# Leaf.net
KiCad netlist of a schematic drawn in Altium Designer
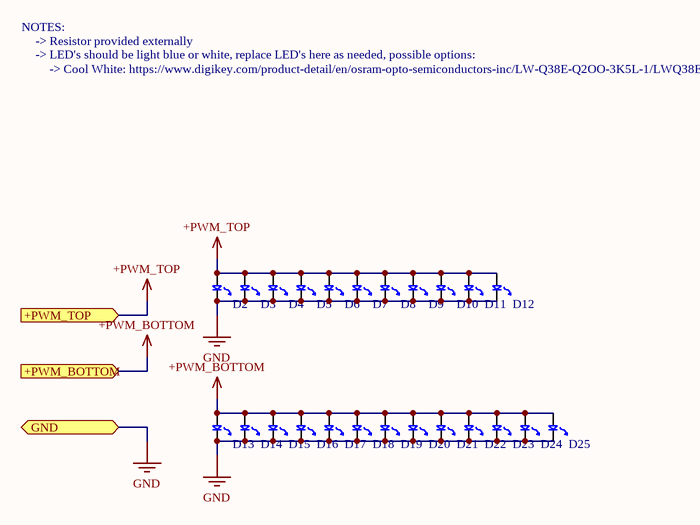
[diagram p0: Leaf.SchDoc]

(export (version "E")
  (design (tool "Eeschema 10.0.6"))
  (components
    (comp (ref "D2")
      (value "LED_LBQ39G_BLUE")
      (footprint "LED_0603P_BLUE")
      (description "Blue 470nm LED Indication - Discrete 2.85V 0603 (1608 Metric)")
      (fields
        (field (name "MANUFACTURER") "OSRAM Opto Semiconductors Inc.")
        (field (name "MANUFACTURER PART NUMBER") "LB Q39G-L2OO-35-1")
      )
      (libsource (lib "SSI") (part "LED_LBQ39G_BLUE"))
    )
    (comp (ref "D3")
      (value "LED_LBQ39G_BLUE")
      (footprint "LED_0603P_BLUE")
      (description "Blue 470nm LED Indication - Discrete 2.85V 0603 (1608 Metric)")
      (fields
        (field (name "MANUFACTURER") "OSRAM Opto Semiconductors Inc.")
        (field (name "MANUFACTURER PART NUMBER") "LB Q39G-L2OO-35-1")
      )
      (libsource (lib "SSI") (part "LED_LBQ39G_BLUE"))
    )
    (comp (ref "D4")
      (value "LED_LBQ39G_BLUE")
      (footprint "LED_0603P_BLUE")
      (description "Blue 470nm LED Indication - Discrete 2.85V 0603 (1608 Metric)")
      (fields
        (field (name "MANUFACTURER") "OSRAM Opto Semiconductors Inc.")
        (field (name "MANUFACTURER PART NUMBER") "LB Q39G-L2OO-35-1")
      )
      (libsource (lib "SSI") (part "LED_LBQ39G_BLUE"))
    )
    (comp (ref "D5")
      (value "LED_LBQ39G_BLUE")
      (footprint "LED_0603P_BLUE")
      (description "Blue 470nm LED Indication - Discrete 2.85V 0603 (1608 Metric)")
      (fields
        (field (name "MANUFACTURER") "OSRAM Opto Semiconductors Inc.")
        (field (name "MANUFACTURER PART NUMBER") "LB Q39G-L2OO-35-1")
      )
      (libsource (lib "SSI") (part "LED_LBQ39G_BLUE"))
    )
    (comp (ref "D6")
      (value "LED_LBQ39G_BLUE")
      (footprint "LED_0603P_BLUE")
      (description "Blue 470nm LED Indication - Discrete 2.85V 0603 (1608 Metric)")
      (fields
        (field (name "MANUFACTURER") "OSRAM Opto Semiconductors Inc.")
        (field (name "MANUFACTURER PART NUMBER") "LB Q39G-L2OO-35-1")
      )
      (libsource (lib "SSI") (part "LED_LBQ39G_BLUE"))
    )
    (comp (ref "D7")
      (value "LED_LBQ39G_BLUE")
      (footprint "LED_0603P_BLUE")
      (description "Blue 470nm LED Indication - Discrete 2.85V 0603 (1608 Metric)")
      (fields
        (field (name "MANUFACTURER") "OSRAM Opto Semiconductors Inc.")
        (field (name "MANUFACTURER PART NUMBER") "LB Q39G-L2OO-35-1")
      )
      (libsource (lib "SSI") (part "LED_LBQ39G_BLUE"))
    )
    (comp (ref "D8")
      (value "LED_LBQ39G_BLUE")
      (footprint "LED_0603P_BLUE")
      (description "Blue 470nm LED Indication - Discrete 2.85V 0603 (1608 Metric)")
      (fields
        (field (name "MANUFACTURER") "OSRAM Opto Semiconductors Inc.")
        (field (name "MANUFACTURER PART NUMBER") "LB Q39G-L2OO-35-1")
      )
      (libsource (lib "SSI") (part "LED_LBQ39G_BLUE"))
    )
    (comp (ref "D9")
      (value "LED_LBQ39G_BLUE")
      (footprint "LED_0603P_BLUE")
      (description "Blue 470nm LED Indication - Discrete 2.85V 0603 (1608 Metric)")
      (fields
        (field (name "MANUFACTURER") "OSRAM Opto Semiconductors Inc.")
        (field (name "MANUFACTURER PART NUMBER") "LB Q39G-L2OO-35-1")
      )
      (libsource (lib "SSI") (part "LED_LBQ39G_BLUE"))
    )
    (comp (ref "D10")
      (value "LED_LBQ39G_BLUE")
      (footprint "LED_0603P_BLUE")
      (description "Blue 470nm LED Indication - Discrete 2.85V 0603 (1608 Metric)")
      (fields
        (field (name "MANUFACTURER") "OSRAM Opto Semiconductors Inc.")
        (field (name "MANUFACTURER PART NUMBER") "LB Q39G-L2OO-35-1")
      )
      (libsource (lib "SSI") (part "LED_LBQ39G_BLUE"))
    )
    (comp (ref "D11")
      (value "LED_LBQ39G_BLUE")
      (footprint "LED_0603P_BLUE")
      (description "Blue 470nm LED Indication - Discrete 2.85V 0603 (1608 Metric)")
      (fields
        (field (name "MANUFACTURER") "OSRAM Opto Semiconductors Inc.")
        (field (name "MANUFACTURER PART NUMBER") "LB Q39G-L2OO-35-1")
      )
      (libsource (lib "SSI") (part "LED_LBQ39G_BLUE"))
    )
    (comp (ref "D12")
      (value "LED_LBQ39G_BLUE")
      (footprint "LED_0603P_BLUE")
      (description "Blue 470nm LED Indication - Discrete 2.85V 0603 (1608 Metric)")
      (fields
        (field (name "MANUFACTURER") "OSRAM Opto Semiconductors Inc.")
        (field (name "MANUFACTURER PART NUMBER") "LB Q39G-L2OO-35-1")
      )
      (libsource (lib "SSI") (part "LED_LBQ39G_BLUE"))
    )
    (comp (ref "D13")
      (value "LED_LBQ39G_BLUE")
      (footprint "LED_0603P_BLUE")
      (description "Blue 470nm LED Indication - Discrete 2.85V 0603 (1608 Metric)")
      (fields
        (field (name "MANUFACTURER") "OSRAM Opto Semiconductors Inc.")
        (field (name "MANUFACTURER PART NUMBER") "LB Q39G-L2OO-35-1")
      )
      (libsource (lib "SSI") (part "LED_LBQ39G_BLUE"))
    )
    (comp (ref "D14")
      (value "LED_LBQ39G_BLUE")
      (footprint "LED_0603P_BLUE")
      (description "Blue 470nm LED Indication - Discrete 2.85V 0603 (1608 Metric)")
      (fields
        (field (name "MANUFACTURER") "OSRAM Opto Semiconductors Inc.")
        (field (name "MANUFACTURER PART NUMBER") "LB Q39G-L2OO-35-1")
      )
      (libsource (lib "SSI") (part "LED_LBQ39G_BLUE"))
    )
    (comp (ref "D15")
      (value "LED_LBQ39G_BLUE")
      (footprint "LED_0603P_BLUE")
      (description "Blue 470nm LED Indication - Discrete 2.85V 0603 (1608 Metric)")
      (fields
        (field (name "MANUFACTURER") "OSRAM Opto Semiconductors Inc.")
        (field (name "MANUFACTURER PART NUMBER") "LB Q39G-L2OO-35-1")
      )
      (libsource (lib "SSI") (part "LED_LBQ39G_BLUE"))
    )
    (comp (ref "D16")
      (value "LED_LBQ39G_BLUE")
      (footprint "LED_0603P_BLUE")
      (description "Blue 470nm LED Indication - Discrete 2.85V 0603 (1608 Metric)")
      (fields
        (field (name "MANUFACTURER") "OSRAM Opto Semiconductors Inc.")
        (field (name "MANUFACTURER PART NUMBER") "LB Q39G-L2OO-35-1")
      )
      (libsource (lib "SSI") (part "LED_LBQ39G_BLUE"))
    )
    (comp (ref "D17")
      (value "LED_LBQ39G_BLUE")
      (footprint "LED_0603P_BLUE")
      (description "Blue 470nm LED Indication - Discrete 2.85V 0603 (1608 Metric)")
      (fields
        (field (name "MANUFACTURER") "OSRAM Opto Semiconductors Inc.")
        (field (name "MANUFACTURER PART NUMBER") "LB Q39G-L2OO-35-1")
      )
      (libsource (lib "SSI") (part "LED_LBQ39G_BLUE"))
    )
    (comp (ref "D18")
      (value "LED_LBQ39G_BLUE")
      (footprint "LED_0603P_BLUE")
      (description "Blue 470nm LED Indication - Discrete 2.85V 0603 (1608 Metric)")
      (fields
        (field (name "MANUFACTURER") "OSRAM Opto Semiconductors Inc.")
        (field (name "MANUFACTURER PART NUMBER") "LB Q39G-L2OO-35-1")
      )
      (libsource (lib "SSI") (part "LED_LBQ39G_BLUE"))
    )
    (comp (ref "D19")
      (value "LED_LBQ39G_BLUE")
      (footprint "LED_0603P_BLUE")
      (description "Blue 470nm LED Indication - Discrete 2.85V 0603 (1608 Metric)")
      (fields
        (field (name "MANUFACTURER") "OSRAM Opto Semiconductors Inc.")
        (field (name "MANUFACTURER PART NUMBER") "LB Q39G-L2OO-35-1")
      )
      (libsource (lib "SSI") (part "LED_LBQ39G_BLUE"))
    )
    (comp (ref "D20")
      (value "LED_LBQ39G_BLUE")
      (footprint "LED_0603P_BLUE")
      (description "Blue 470nm LED Indication - Discrete 2.85V 0603 (1608 Metric)")
      (fields
        (field (name "MANUFACTURER") "OSRAM Opto Semiconductors Inc.")
        (field (name "MANUFACTURER PART NUMBER") "LB Q39G-L2OO-35-1")
      )
      (libsource (lib "SSI") (part "LED_LBQ39G_BLUE"))
    )
    (comp (ref "D21")
      (value "LED_LBQ39G_BLUE")
      (footprint "LED_0603P_BLUE")
      (description "Blue 470nm LED Indication - Discrete 2.85V 0603 (1608 Metric)")
      (fields
        (field (name "MANUFACTURER") "OSRAM Opto Semiconductors Inc.")
        (field (name "MANUFACTURER PART NUMBER") "LB Q39G-L2OO-35-1")
      )
      (libsource (lib "SSI") (part "LED_LBQ39G_BLUE"))
    )
    (comp (ref "D22")
      (value "LED_LBQ39G_BLUE")
      (footprint "LED_0603P_BLUE")
      (description "Blue 470nm LED Indication - Discrete 2.85V 0603 (1608 Metric)")
      (fields
        (field (name "MANUFACTURER") "OSRAM Opto Semiconductors Inc.")
        (field (name "MANUFACTURER PART NUMBER") "LB Q39G-L2OO-35-1")
      )
      (libsource (lib "SSI") (part "LED_LBQ39G_BLUE"))
    )
    (comp (ref "D23")
      (value "LED_LBQ39G_BLUE")
      (footprint "LED_0603P_BLUE")
      (description "Blue 470nm LED Indication - Discrete 2.85V 0603 (1608 Metric)")
      (fields
        (field (name "MANUFACTURER") "OSRAM Opto Semiconductors Inc.")
        (field (name "MANUFACTURER PART NUMBER") "LB Q39G-L2OO-35-1")
      )
      (libsource (lib "SSI") (part "LED_LBQ39G_BLUE"))
    )
    (comp (ref "D24")
      (value "LED_LBQ39G_BLUE")
      (footprint "LED_0603P_BLUE")
      (description "Blue 470nm LED Indication - Discrete 2.85V 0603 (1608 Metric)")
      (fields
        (field (name "MANUFACTURER") "OSRAM Opto Semiconductors Inc.")
        (field (name "MANUFACTURER PART NUMBER") "LB Q39G-L2OO-35-1")
      )
      (libsource (lib "SSI") (part "LED_LBQ39G_BLUE"))
    )
    (comp (ref "D25")
      (value "LED_LBQ39G_BLUE")
      (footprint "LED_0603P_BLUE")
      (description "Blue 470nm LED Indication - Discrete 2.85V 0603 (1608 Metric)")
      (fields
        (field (name "MANUFACTURER") "OSRAM Opto Semiconductors Inc.")
        (field (name "MANUFACTURER PART NUMBER") "LB Q39G-L2OO-35-1")
      )
      (libsource (lib "SSI") (part "LED_LBQ39G_BLUE"))
    )
  )
  (nets
    (net (code "1") (name "+PWM_BOTTOM") (class "Default")
      (node (ref "D13") (pin "2") (pintype "passive"))
      (node (ref "D14") (pin "2") (pintype "passive"))
      (node (ref "D15") (pin "2") (pintype "passive"))
      (node (ref "D16") (pin "2") (pintype "passive"))
      (node (ref "D17") (pin "2") (pintype "passive"))
      (node (ref "D18") (pin "2") (pintype "passive"))
      (node (ref "D19") (pin "2") (pintype "passive"))
      (node (ref "D20") (pin "2") (pintype "passive"))
      (node (ref "D21") (pin "2") (pintype "passive"))
      (node (ref "D22") (pin "2") (pintype "passive"))
      (node (ref "D23") (pin "2") (pintype "passive"))
      (node (ref "D24") (pin "2") (pintype "passive"))
      (node (ref "D25") (pin "2") (pintype "passive"))
    )
    (net (code "2") (name "+PWM_TOP") (class "Default")
      (node (ref "D10") (pin "2") (pintype "passive"))
      (node (ref "D11") (pin "2") (pintype "passive"))
      (node (ref "D12") (pin "2") (pintype "passive"))
      (node (ref "D2") (pin "2") (pintype "passive"))
      (node (ref "D3") (pin "2") (pintype "passive"))
      (node (ref "D4") (pin "2") (pintype "passive"))
      (node (ref "D5") (pin "2") (pintype "passive"))
      (node (ref "D6") (pin "2") (pintype "passive"))
      (node (ref "D7") (pin "2") (pintype "passive"))
      (node (ref "D8") (pin "2") (pintype "passive"))
      (node (ref "D9") (pin "2") (pintype "passive"))
    )
    (net (code "3") (name "GND") (class "Default")
      (node (ref "D10") (pin "1") (pintype "passive"))
      (node (ref "D11") (pin "1") (pintype "passive"))
      (node (ref "D12") (pin "1") (pintype "passive"))
      (node (ref "D13") (pin "1") (pintype "passive"))
      (node (ref "D14") (pin "1") (pintype "passive"))
      (node (ref "D15") (pin "1") (pintype "passive"))
      (node (ref "D16") (pin "1") (pintype "passive"))
      (node (ref "D17") (pin "1") (pintype "passive"))
      (node (ref "D18") (pin "1") (pintype "passive"))
      (node (ref "D19") (pin "1") (pintype "passive"))
      (node (ref "D2") (pin "1") (pintype "passive"))
      (node (ref "D20") (pin "1") (pintype "passive"))
      (node (ref "D21") (pin "1") (pintype "passive"))
      (node (ref "D22") (pin "1") (pintype "passive"))
      (node (ref "D23") (pin "1") (pintype "passive"))
      (node (ref "D24") (pin "1") (pintype "passive"))
      (node (ref "D25") (pin "1") (pintype "passive"))
      (node (ref "D3") (pin "1") (pintype "passive"))
      (node (ref "D4") (pin "1") (pintype "passive"))
      (node (ref "D5") (pin "1") (pintype "passive"))
      (node (ref "D6") (pin "1") (pintype "passive"))
      (node (ref "D7") (pin "1") (pintype "passive"))
      (node (ref "D8") (pin "1") (pintype "passive"))
      (node (ref "D9") (pin "1") (pintype "passive"))
    )
  )
)
